# slide_sensor.net
KiCad netlist of a schematic drawn in EAGLE
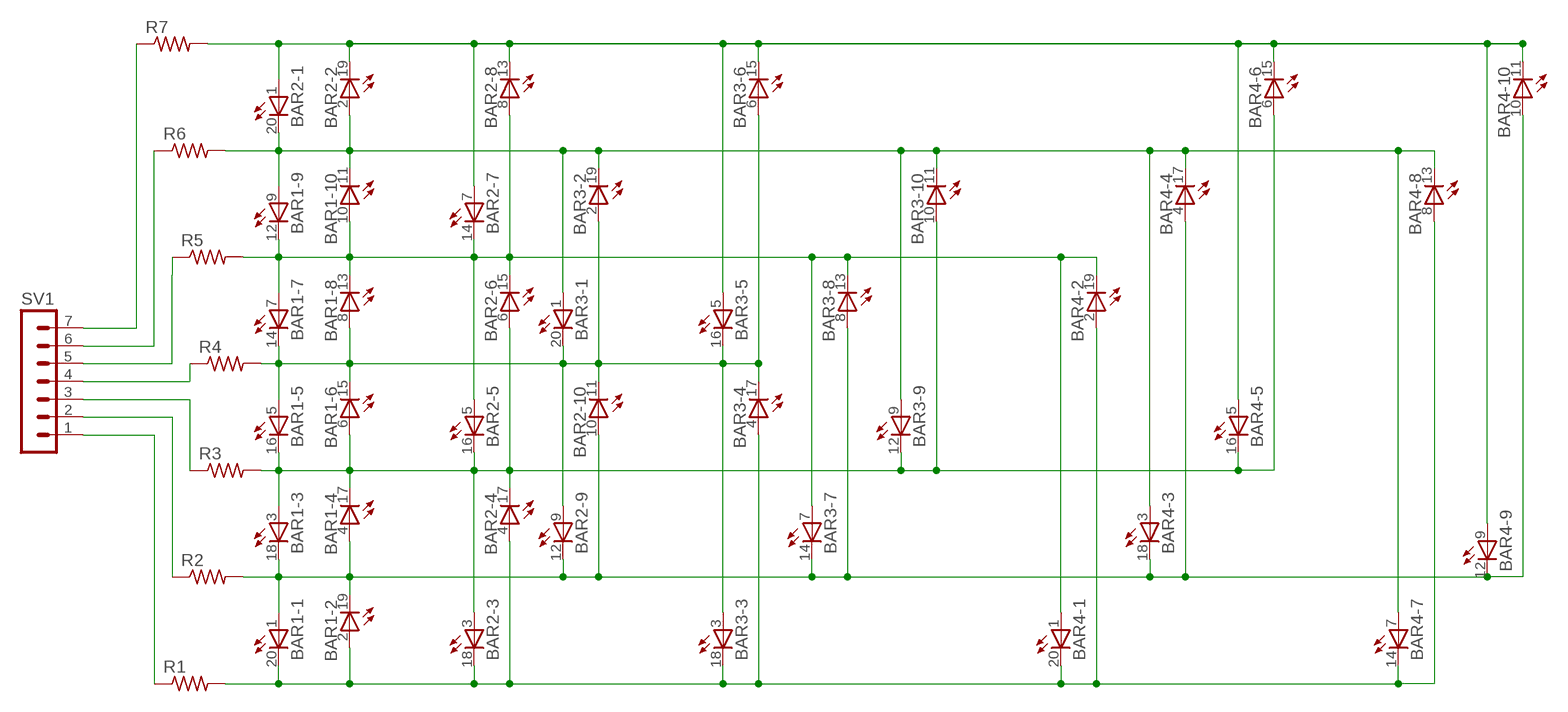
[diagram p0: schematic, sheet 1]

(export (version "E")
  (design (tool "Eeschema 10.0.6"))
  (components
    (comp (ref "BAR1")
      (value "LB10")
      (footprint "eagle-import:LB10")
      (libsource (lib "eagle-import") (part "LB10"))
    )
    (comp (ref "BAR2")
      (value "LB10")
      (footprint "eagle-import:LB10")
      (libsource (lib "eagle-import") (part "LB10"))
    )
    (comp (ref "BAR3")
      (value "LB10")
      (footprint "eagle-import:LB10")
      (libsource (lib "eagle-import") (part "LB10"))
    )
    (comp (ref "BAR4")
      (value "LB10")
      (footprint "eagle-import:LB10")
      (libsource (lib "eagle-import") (part "LB10"))
    )
    (comp (ref "R1")
      (value "R-US_0207/7")
      (footprint "eagle-import:0207_7")
      (libsource (lib "eagle-import") (part "R-US_0207/7"))
    )
    (comp (ref "R2")
      (value "R-US_0207/7")
      (footprint "eagle-import:0207_7")
      (libsource (lib "eagle-import") (part "R-US_0207/7"))
    )
    (comp (ref "R3")
      (value "R-US_0207/7")
      (footprint "eagle-import:0207_7")
      (libsource (lib "eagle-import") (part "R-US_0207/7"))
    )
    (comp (ref "R4")
      (value "R-US_0207/7")
      (footprint "eagle-import:0207_7")
      (libsource (lib "eagle-import") (part "R-US_0207/7"))
    )
    (comp (ref "R5")
      (value "R-US_0207/7")
      (footprint "eagle-import:0207_7")
      (libsource (lib "eagle-import") (part "R-US_0207/7"))
    )
    (comp (ref "R6")
      (value "R-US_0207/7")
      (footprint "eagle-import:0207_7")
      (libsource (lib "eagle-import") (part "R-US_0207/7"))
    )
    (comp (ref "R7")
      (value "R-US_0207/7")
      (footprint "eagle-import:0207_7")
      (libsource (lib "eagle-import") (part "R-US_0207/7"))
    )
    (comp (ref "SV1")
      (value "MA07-1")
      (footprint "eagle-import:MA07-1")
      (libsource (lib "eagle-import") (part "MA07-1"))
    )
  )
  (nets
    (net (code "1") (name "Net-(BAR1A-A)") (class "Default")
      (node (ref "BAR1") (pin "1") (pinfunction "A_1") (pintype "passive"))
      (node (ref "BAR1") (pin "18") (pinfunction "C_18") (pintype "passive"))
      (node (ref "BAR1") (pin "19") (pinfunction "C_19") (pintype "passive"))
      (node (ref "BAR1") (pin "4") (pinfunction "A_4") (pintype "passive"))
      (node (ref "BAR2") (pin "10") (pinfunction "A_10") (pintype "passive"))
      (node (ref "BAR2") (pin "12") (pinfunction "C_12") (pintype "passive"))
      (node (ref "BAR3") (pin "14") (pinfunction "C_14") (pintype "passive"))
      (node (ref "BAR3") (pin "8") (pinfunction "A_8") (pintype "passive"))
      (node (ref "BAR4") (pin "10") (pinfunction "A_10") (pintype "passive"))
      (node (ref "BAR4") (pin "12") (pinfunction "C_12") (pintype "passive"))
      (node (ref "BAR4") (pin "18") (pinfunction "C_18") (pintype "passive"))
      (node (ref "BAR4") (pin "4") (pinfunction "A_4") (pintype "passive"))
      (node (ref "R2") (pin "2") (pinfunction "2_2") (pintype "passive"))
    )
    (net (code "2") (name "Net-(BAR1A-C)") (class "Default")
      (node (ref "BAR1") (pin "2") (pinfunction "A_2") (pintype "passive"))
      (node (ref "BAR1") (pin "20") (pinfunction "C_20") (pintype "passive"))
      (node (ref "BAR2") (pin "18") (pinfunction "C_18") (pintype "passive"))
      (node (ref "BAR2") (pin "4") (pinfunction "A_4") (pintype "passive"))
      (node (ref "BAR3") (pin "18") (pinfunction "C_18") (pintype "passive"))
      (node (ref "BAR3") (pin "4") (pinfunction "A_4") (pintype "passive"))
      (node (ref "BAR4") (pin "14") (pinfunction "C_14") (pintype "passive"))
      (node (ref "BAR4") (pin "2") (pinfunction "A_2") (pintype "passive"))
      (node (ref "BAR4") (pin "20") (pinfunction "C_20") (pintype "passive"))
      (node (ref "BAR4") (pin "8") (pinfunction "A_8") (pintype "passive"))
      (node (ref "R1") (pin "2") (pinfunction "2_2") (pintype "passive"))
    )
    (net (code "3") (name "Net-(BAR1B-A)") (class "Default")
      (node (ref "BAR1") (pin "10") (pinfunction "A_10") (pintype "passive"))
      (node (ref "BAR1") (pin "12") (pinfunction "C_12") (pintype "passive"))
      (node (ref "BAR1") (pin "13") (pinfunction "C_13") (pintype "passive"))
      (node (ref "BAR1") (pin "7") (pinfunction "A_7") (pintype "passive"))
      (node (ref "BAR2") (pin "14") (pinfunction "C_14") (pintype "passive"))
      (node (ref "BAR2") (pin "15") (pinfunction "C_15") (pintype "passive"))
      (node (ref "BAR2") (pin "5") (pinfunction "A_5") (pintype "passive"))
      (node (ref "BAR2") (pin "8") (pinfunction "A_8") (pintype "passive"))
      (node (ref "BAR3") (pin "13") (pinfunction "C_13") (pintype "passive"))
      (node (ref "BAR3") (pin "7") (pinfunction "A_7") (pintype "passive"))
      (node (ref "BAR4") (pin "1") (pinfunction "A_1") (pintype "passive"))
      (node (ref "BAR4") (pin "19") (pinfunction "C_19") (pintype "passive"))
      (node (ref "R5") (pin "2") (pinfunction "2_2") (pintype "passive"))
    )
    (net (code "4") (name "Net-(BAR1B-C)") (class "Default")
      (node (ref "BAR1") (pin "11") (pinfunction "C_11") (pintype "passive"))
      (node (ref "BAR1") (pin "9") (pinfunction "A_9") (pintype "passive"))
      (node (ref "BAR2") (pin "2") (pinfunction "A_2") (pintype "passive"))
      (node (ref "BAR2") (pin "20") (pinfunction "C_20") (pintype "passive"))
      (node (ref "BAR3") (pin "1") (pinfunction "A_1") (pintype "passive"))
      (node (ref "BAR3") (pin "11") (pinfunction "C_11") (pintype "passive"))
      (node (ref "BAR3") (pin "19") (pinfunction "C_19") (pintype "passive"))
      (node (ref "BAR3") (pin "9") (pinfunction "A_9") (pintype "passive"))
      (node (ref "BAR4") (pin "13") (pinfunction "C_13") (pintype "passive"))
      (node (ref "BAR4") (pin "17") (pinfunction "C_17") (pintype "passive"))
      (node (ref "BAR4") (pin "3") (pinfunction "A_3") (pintype "passive"))
      (node (ref "BAR4") (pin "7") (pinfunction "A_7") (pintype "passive"))
      (node (ref "R6") (pin "2") (pinfunction "2_2") (pintype "passive"))
    )
    (net (code "5") (name "Net-(BAR1D-A)") (class "Default")
      (node (ref "BAR1") (pin "16") (pinfunction "C_16") (pintype "passive"))
      (node (ref "BAR1") (pin "17") (pinfunction "C_17") (pintype "passive"))
      (node (ref "BAR1") (pin "3") (pinfunction "A_3") (pintype "passive"))
      (node (ref "BAR1") (pin "6") (pinfunction "A_6") (pintype "passive"))
      (node (ref "BAR2") (pin "16") (pinfunction "C_16") (pintype "passive"))
      (node (ref "BAR2") (pin "17") (pinfunction "C_17") (pintype "passive"))
      (node (ref "BAR2") (pin "3") (pinfunction "A_3") (pintype "passive"))
      (node (ref "BAR2") (pin "6") (pinfunction "A_6") (pintype "passive"))
      (node (ref "BAR3") (pin "10") (pinfunction "A_10") (pintype "passive"))
      (node (ref "BAR3") (pin "12") (pinfunction "C_12") (pintype "passive"))
      (node (ref "BAR4") (pin "16") (pinfunction "C_16") (pintype "passive"))
      (node (ref "BAR4") (pin "6") (pinfunction "A_6") (pintype "passive"))
      (node (ref "R3") (pin "2") (pinfunction "2_2") (pintype "passive"))
    )
    (net (code "6") (name "Net-(BAR1F-A)") (class "Default")
      (node (ref "BAR1") (pin "14") (pinfunction "C_14") (pintype "passive"))
      (node (ref "BAR1") (pin "15") (pinfunction "C_15") (pintype "passive"))
      (node (ref "BAR1") (pin "5") (pinfunction "A_5") (pintype "passive"))
      (node (ref "BAR1") (pin "8") (pinfunction "A_8") (pintype "passive"))
      (node (ref "BAR2") (pin "11") (pinfunction "C_11") (pintype "passive"))
      (node (ref "BAR2") (pin "9") (pinfunction "A_9") (pintype "passive"))
      (node (ref "BAR3") (pin "16") (pinfunction "C_16") (pintype "passive"))
      (node (ref "BAR3") (pin "17") (pinfunction "C_17") (pintype "passive"))
      (node (ref "BAR3") (pin "2") (pinfunction "A_2") (pintype "passive"))
      (node (ref "BAR3") (pin "20") (pinfunction "C_20") (pintype "passive"))
      (node (ref "BAR3") (pin "3") (pinfunction "A_3") (pintype "passive"))
      (node (ref "BAR3") (pin "6") (pinfunction "A_6") (pintype "passive"))
      (node (ref "R4") (pin "2") (pinfunction "2_2") (pintype "passive"))
    )
    (net (code "7") (name "Net-(BAR2A-A)") (class "Default")
      (node (ref "BAR2") (pin "1") (pinfunction "A_1") (pintype "passive"))
      (node (ref "BAR2") (pin "13") (pinfunction "C_13") (pintype "passive"))
      (node (ref "BAR2") (pin "19") (pinfunction "C_19") (pintype "passive"))
      (node (ref "BAR2") (pin "7") (pinfunction "A_7") (pintype "passive"))
      (node (ref "BAR3") (pin "15") (pinfunction "C_15") (pintype "passive"))
      (node (ref "BAR3") (pin "5") (pinfunction "A_5") (pintype "passive"))
      (node (ref "BAR4") (pin "11") (pinfunction "C_11") (pintype "passive"))
      (node (ref "BAR4") (pin "15") (pinfunction "C_15") (pintype "passive"))
      (node (ref "BAR4") (pin "5") (pinfunction "A_5") (pintype "passive"))
      (node (ref "BAR4") (pin "9") (pinfunction "A_9") (pintype "passive"))
      (node (ref "R7") (pin "2") (pinfunction "2_2") (pintype "passive"))
    )
    (net (code "8") (name "Net-(R1-Pad1)") (class "Default")
      (node (ref "R1") (pin "1") (pinfunction "1_1") (pintype "passive"))
      (node (ref "SV1") (pin "1") (pinfunction "1_1") (pintype "passive"))
    )
    (net (code "9") (name "Net-(R2-Pad1)") (class "Default")
      (node (ref "R2") (pin "1") (pinfunction "1_1") (pintype "passive"))
      (node (ref "SV1") (pin "2") (pinfunction "2_2") (pintype "passive"))
    )
    (net (code "10") (name "Net-(R3-Pad1)") (class "Default")
      (node (ref "R3") (pin "1") (pinfunction "1_1") (pintype "passive"))
      (node (ref "SV1") (pin "3") (pinfunction "3_3") (pintype "passive"))
    )
    (net (code "11") (name "Net-(R4-Pad1)") (class "Default")
      (node (ref "R4") (pin "1") (pinfunction "1_1") (pintype "passive"))
      (node (ref "SV1") (pin "4") (pinfunction "4_4") (pintype "passive"))
    )
    (net (code "12") (name "Net-(R5-Pad1)") (class "Default")
      (node (ref "R5") (pin "1") (pinfunction "1_1") (pintype "passive"))
      (node (ref "SV1") (pin "5") (pinfunction "5_5") (pintype "passive"))
    )
    (net (code "13") (name "Net-(R6-Pad1)") (class "Default")
      (node (ref "R6") (pin "1") (pinfunction "1_1") (pintype "passive"))
      (node (ref "SV1") (pin "6") (pinfunction "6_6") (pintype "passive"))
    )
    (net (code "14") (name "Net-(R7-Pad1)") (class "Default")
      (node (ref "R7") (pin "1") (pinfunction "1_1") (pintype "passive"))
      (node (ref "SV1") (pin "7") (pinfunction "7_7") (pintype "passive"))
    )
  )
)
